# 02_-_MCU.net
KiCad netlist of a schematic drawn in Altium Designer
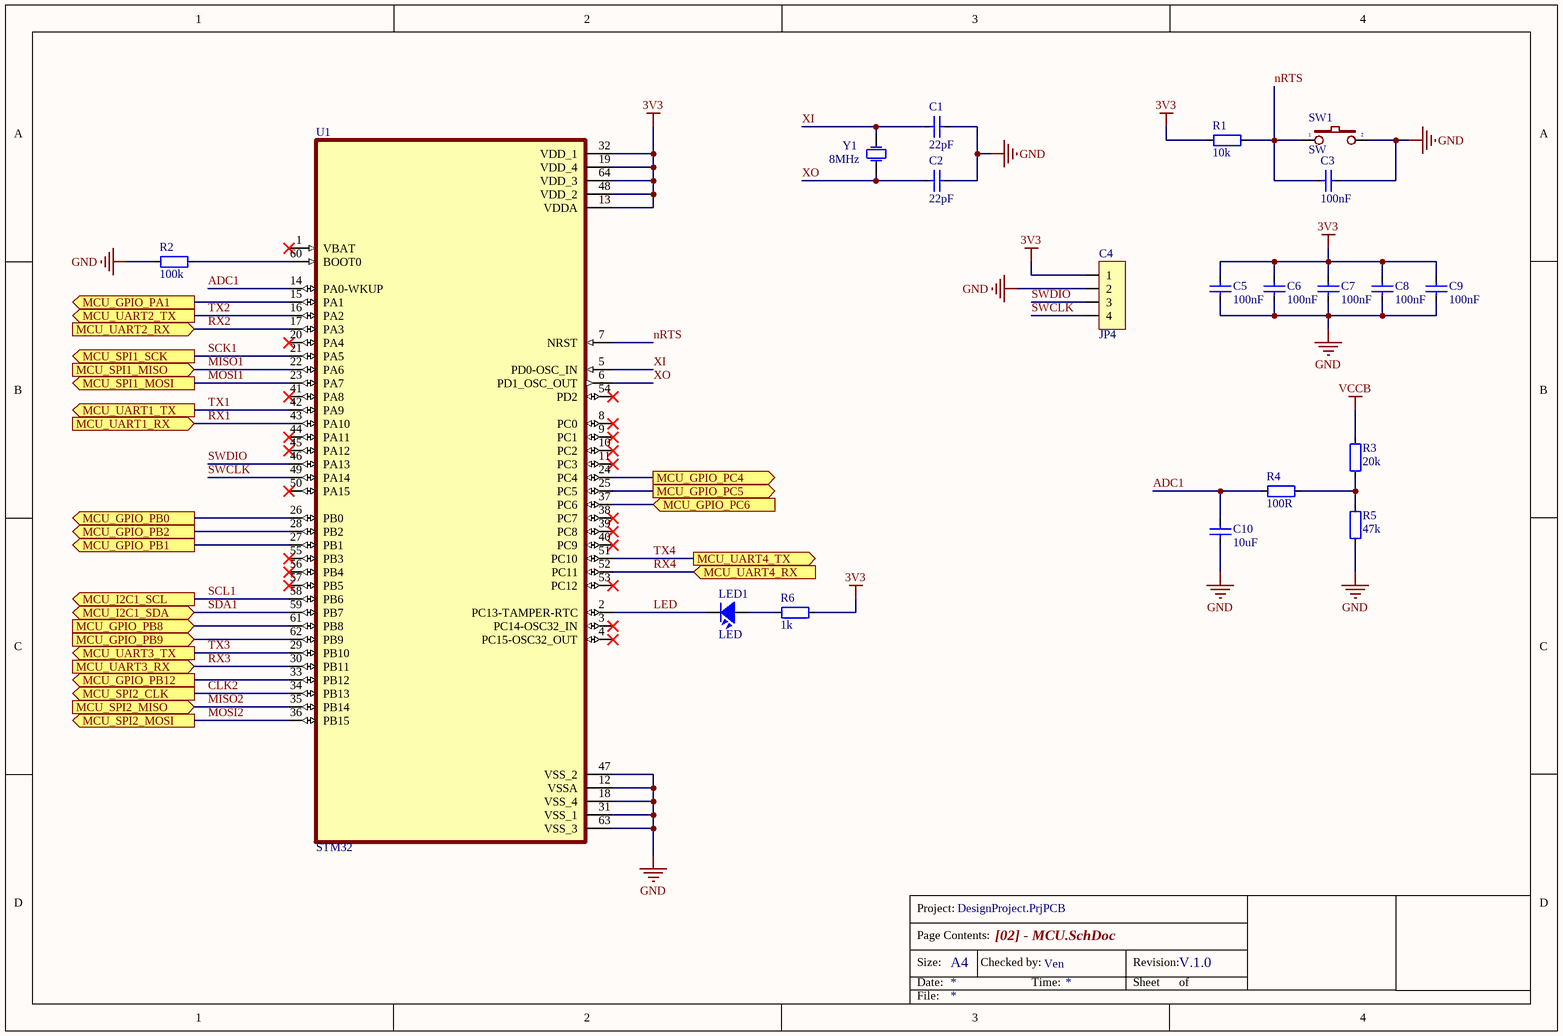
[diagram p0: [02] - MCU.SchDoc]

(export (version "E")
  (design (tool "Eeschema 10.0.6"))
  (components
    (comp (ref "C1")
      (value "22pF")
      (footprint "CAP_0603")
      (description "Capacitor")
      (fields (field (name "PUBLISHER") "Altium Limited"))
      (libsource (lib "My Library") (part "CapSMD"))
    )
    (comp (ref "C2")
      (value "22pF")
      (footprint "CAP_0603")
      (description "Capacitor")
      (fields (field (name "PUBLISHER") "Altium Limited"))
      (libsource (lib "My Library") (part "CapSMD"))
    )
    (comp (ref "C3")
      (value "100nF")
      (footprint "CAP_0603")
      (description "Capacitor")
      (fields (field (name "PUBLISHER") "Altium Limited"))
      (libsource (lib "My Library") (part "CapSMD"))
    )
    (comp (ref "C4")
      (value "JP4")
      (footprint "JP4-C1T")
      (description "WR-PHD 2.54 mm Angled Socket Header")
      (fields
        (field (name "MANUFACTURER") "Würth Elektronik eiSos GmbH")
        (field (name "PARTNO") "613004143121")
        (field (name "CREATED BY") "Karrer Zheng")
      )
      (libsource (lib "My Library") (part "JP4"))
    )
    (comp (ref "C5")
      (value "100nF")
      (footprint "CAP_0603")
      (description "Capacitor")
      (fields (field (name "PUBLISHER") "Altium Limited"))
      (libsource (lib "My Library") (part "CapSMD"))
    )
    (comp (ref "C6")
      (value "100nF")
      (footprint "CAP_0603")
      (description "Capacitor")
      (fields (field (name "PUBLISHER") "Altium Limited"))
      (libsource (lib "My Library") (part "CapSMD"))
    )
    (comp (ref "C7")
      (value "100nF")
      (footprint "CAP_0603")
      (description "Capacitor")
      (fields (field (name "PUBLISHER") "Altium Limited"))
      (libsource (lib "My Library") (part "CapSMD"))
    )
    (comp (ref "C8")
      (value "100nF")
      (footprint "CAP_0603")
      (description "Capacitor")
      (fields (field (name "PUBLISHER") "Altium Limited"))
      (libsource (lib "My Library") (part "CapSMD"))
    )
    (comp (ref "C9")
      (value "100nF")
      (footprint "CAP_0603")
      (description "Capacitor")
      (fields (field (name "PUBLISHER") "Altium Limited"))
      (libsource (lib "My Library") (part "CapSMD"))
    )
    (comp (ref "C10")
      (value "10uF")
      (footprint "CAP_0603")
      (description "Capacitor")
      (fields (field (name "PUBLISHER") "Altium Limited"))
      (libsource (lib "My Library") (part "CapSMD"))
    )
    (comp (ref "LED1")
      (value "LED")
      (footprint "LED-0805-Red")
      (description "LED Single colour Green and Red")
      (libsource (lib "My Library") (part "LED"))
    )
    (comp (ref "R1")
      (value "10k")
      (footprint "RES-SMD-0603")
      (description "Resistor")
      (fields
        (field (name "MANUFACTURER") "Generic Components")
        (field (name "PUBLISHER") "Altium Hobart Technology Centre")
      )
      (libsource (lib "My Library") (part "Resistor - SMD"))
    )
    (comp (ref "R2")
      (value "100k")
      (footprint "RES-SMD-0603")
      (description "Resistor")
      (fields
        (field (name "MANUFACTURER") "Generic Components")
        (field (name "PUBLISHER") "Altium Hobart Technology Centre")
      )
      (libsource (lib "My Library") (part "Resistor - SMD"))
    )
    (comp (ref "R3")
      (value "20k")
      (footprint "RES-SMD-0603")
      (description "Resistor")
      (fields
        (field (name "MANUFACTURER") "Generic Components")
        (field (name "PUBLISHER") "Altium Hobart Technology Centre")
      )
      (libsource (lib "My Library") (part "Resistor - SMD"))
    )
    (comp (ref "R4")
      (value "100R")
      (footprint "RES-SMD-0603")
      (description "Resistor")
      (fields
        (field (name "MANUFACTURER") "Generic Components")
        (field (name "PUBLISHER") "Altium Hobart Technology Centre")
      )
      (libsource (lib "My Library") (part "Resistor - SMD"))
    )
    (comp (ref "R5")
      (value "47k")
      (footprint "RES-SMD-0603")
      (description "Resistor")
      (fields
        (field (name "MANUFACTURER") "Generic Components")
        (field (name "PUBLISHER") "Altium Hobart Technology Centre")
      )
      (libsource (lib "My Library") (part "Resistor - SMD"))
    )
    (comp (ref "R6")
      (value "1k")
      (footprint "RES-SMD-0603")
      (description "Resistor")
      (fields
        (field (name "MANUFACTURER") "Generic Components")
        (field (name "PUBLISHER") "Altium Hobart Technology Centre")
      )
      (libsource (lib "My Library") (part "Resistor - SMD"))
    )
    (comp (ref "SW1")
      (value "SW")
      (footprint "SW2")
      (description "Switch button 2 pin")
      (libsource (lib "My Library") (part "SW2"))
    )
    (comp (ref "U1")
      (value "STM32")
      (footprint "QFP50P1200X1200X160-64N")
      (description "STM32 ARM-based 32-bit MCU 72MHz 256KB")
      (libsource (lib "My Library") (part "STM32F103RCT6"))
    )
    (comp (ref "Y1")
      (value "8MHz")
      (footprint "XTAL 5032 SMD")
      (description "Crystal Oscillator")
      (fields (field (name "PUBLISHER") "Altium Limited"))
      (libsource (lib "My Library") (part "XTAL"))
    )
  )
  (nets
    (net (code "1") (name "/ADC1") (class "Default")
      (node (ref "C10") (pin "1") (pinfunction "1_1") (pintype "passive"))
      (node (ref "R4") (pin "1") (pinfunction "1_1") (pintype "passive"))
      (node (ref "U1") (pin "14") (pinfunction "PA0-WKUP_14") (pintype "bidirectional"))
    )
    (net (code "2") (name "/CLK2") (class "Default")
      (node (ref "U1") (pin "34") (pinfunction "PB13_34") (pintype "bidirectional"))
    )
    (net (code "3") (name "/LED") (class "Default")
      (node (ref "LED1") (pin "2") (pinfunction "2_2") (pintype "passive"))
      (node (ref "U1") (pin "2") (pinfunction "PC13-TAMPER-RTC_2") (pintype "bidirectional"))
    )
    (net (code "4") (name "/MCU_GPIO_PA1") (class "Default")
      (node (ref "U1") (pin "15") (pinfunction "PA1_15") (pintype "bidirectional"))
    )
    (net (code "5") (name "/MCU_GPIO_PB0") (class "Default")
      (node (ref "U1") (pin "26") (pinfunction "PB0_26") (pintype "bidirectional"))
    )
    (net (code "6") (name "/MCU_GPIO_PB1") (class "Default")
      (node (ref "U1") (pin "27") (pinfunction "PB1_27") (pintype "bidirectional"))
    )
    (net (code "7") (name "/MCU_GPIO_PB2") (class "Default")
      (node (ref "U1") (pin "28") (pinfunction "PB2_28") (pintype "bidirectional"))
    )
    (net (code "8") (name "/MCU_GPIO_PB8") (class "Default")
      (node (ref "U1") (pin "61") (pinfunction "PB8_61") (pintype "bidirectional"))
    )
    (net (code "9") (name "/MCU_GPIO_PB9") (class "Default")
      (node (ref "U1") (pin "62") (pinfunction "PB9_62") (pintype "bidirectional"))
    )
    (net (code "10") (name "/MCU_GPIO_PB12") (class "Default")
      (node (ref "U1") (pin "33") (pinfunction "PB12_33") (pintype "bidirectional"))
    )
    (net (code "11") (name "/MCU_GPIO_PC4") (class "Default")
      (node (ref "U1") (pin "24") (pinfunction "PC4_24") (pintype "bidirectional"))
    )
    (net (code "12") (name "/MCU_GPIO_PC5") (class "Default")
      (node (ref "U1") (pin "25") (pinfunction "PC5_25") (pintype "bidirectional"))
    )
    (net (code "13") (name "/MCU_GPIO_PC6") (class "Default")
      (node (ref "U1") (pin "37") (pinfunction "PC6_37") (pintype "bidirectional"))
    )
    (net (code "14") (name "/MISO1") (class "Default")
      (node (ref "U1") (pin "22") (pinfunction "PA6_22") (pintype "bidirectional"))
    )
    (net (code "15") (name "/MISO2") (class "Default")
      (node (ref "U1") (pin "35") (pinfunction "PB14_35") (pintype "bidirectional"))
    )
    (net (code "16") (name "/MOSI1") (class "Default")
      (node (ref "U1") (pin "23") (pinfunction "PA7_23") (pintype "bidirectional"))
    )
    (net (code "17") (name "/MOSI2") (class "Default")
      (node (ref "U1") (pin "36") (pinfunction "PB15_36") (pintype "bidirectional"))
    )
    (net (code "18") (name "/RX1") (class "Default")
      (node (ref "U1") (pin "43") (pinfunction "PA10_43") (pintype "bidirectional"))
    )
    (net (code "19") (name "/RX2") (class "Default")
      (node (ref "U1") (pin "17") (pinfunction "PA3_17") (pintype "bidirectional"))
    )
    (net (code "20") (name "/RX3") (class "Default")
      (node (ref "U1") (pin "30") (pinfunction "PB11_30") (pintype "bidirectional"))
    )
    (net (code "21") (name "/RX4") (class "Default")
      (node (ref "U1") (pin "52") (pinfunction "PC11_52") (pintype "bidirectional"))
    )
    (net (code "22") (name "/SCK1") (class "Default")
      (node (ref "U1") (pin "21") (pinfunction "PA5_21") (pintype "bidirectional"))
    )
    (net (code "23") (name "/SCL1") (class "Default")
      (node (ref "U1") (pin "58") (pinfunction "PB6_58") (pintype "bidirectional"))
    )
    (net (code "24") (name "/SDA1") (class "Default")
      (node (ref "U1") (pin "59") (pinfunction "PB7_59") (pintype "bidirectional"))
    )
    (net (code "25") (name "/SWCLK") (class "Default")
      (node (ref "C4") (pin "4") (pinfunction "4_4") (pintype "passive"))
      (node (ref "U1") (pin "49") (pinfunction "PA14_49") (pintype "bidirectional"))
    )
    (net (code "26") (name "/SWDIO") (class "Default")
      (node (ref "C4") (pin "3") (pinfunction "3_3") (pintype "passive"))
      (node (ref "U1") (pin "46") (pinfunction "PA13_46") (pintype "bidirectional"))
    )
    (net (code "27") (name "/TX1") (class "Default")
      (node (ref "U1") (pin "42") (pinfunction "PA9_42") (pintype "bidirectional"))
    )
    (net (code "28") (name "/TX2") (class "Default")
      (node (ref "U1") (pin "16") (pinfunction "PA2_16") (pintype "bidirectional"))
    )
    (net (code "29") (name "/TX3") (class "Default")
      (node (ref "U1") (pin "29") (pinfunction "PB10_29") (pintype "bidirectional"))
    )
    (net (code "30") (name "/TX4") (class "Default")
      (node (ref "U1") (pin "51") (pinfunction "PC10_51") (pintype "bidirectional"))
    )
    (net (code "31") (name "/XI") (class "Default")
      (node (ref "C1") (pin "2") (pinfunction "2_2") (pintype "passive"))
      (node (ref "U1") (pin "5") (pinfunction "PD0-OSC_IN_5") (pintype "input"))
      (node (ref "Y1") (pin "2") (pinfunction "OSC2_2") (pintype "passive"))
    )
    (net (code "32") (name "/XO") (class "Default")
      (node (ref "C2") (pin "2") (pinfunction "2_2") (pintype "passive"))
      (node (ref "U1") (pin "6") (pinfunction "PD1_OSC_OUT_6") (pintype "output"))
      (node (ref "Y1") (pin "1") (pinfunction "OSC1_1") (pintype "passive"))
    )
    (net (code "33") (name "/nRTS") (class "Default")
      (node (ref "C3") (pin "2") (pinfunction "2_2") (pintype "passive"))
      (node (ref "R1") (pin "2") (pinfunction "2_2") (pintype "passive"))
      (node (ref "SW1") (pin "1") (pinfunction "1_1") (pintype "passive"))
      (node (ref "U1") (pin "7") (pinfunction "NRST_7") (pintype "input"))
    )
    (net (code "34") (name "3V3") (class "Default")
      (node (ref "C4") (pin "1") (pinfunction "1_1") (pintype "passive"))
      (node (ref "C5") (pin "2") (pinfunction "2_2") (pintype "passive"))
      (node (ref "C6") (pin "2") (pinfunction "2_2") (pintype "passive"))
      (node (ref "C7") (pin "2") (pinfunction "2_2") (pintype "passive"))
      (node (ref "C8") (pin "2") (pinfunction "2_2") (pintype "passive"))
      (node (ref "C9") (pin "2") (pinfunction "2_2") (pintype "passive"))
      (node (ref "R1") (pin "1") (pinfunction "1_1") (pintype "passive"))
      (node (ref "R6") (pin "1") (pinfunction "1_1") (pintype "passive"))
      (node (ref "U1") (pin "13") (pinfunction "VDDA_13") (pintype "power_in"))
      (node (ref "U1") (pin "19") (pinfunction "VDD_4_19") (pintype "power_in"))
      (node (ref "U1") (pin "32") (pinfunction "VDD_1_32") (pintype "power_in"))
      (node (ref "U1") (pin "48") (pinfunction "VDD_2_48") (pintype "power_in"))
      (node (ref "U1") (pin "64") (pinfunction "VDD_3_64") (pintype "power_in"))
    )
    (net (code "35") (name "GND") (class "Default")
      (node (ref "C1") (pin "1") (pinfunction "1_1") (pintype "passive"))
      (node (ref "C10") (pin "2") (pinfunction "2_2") (pintype "passive"))
      (node (ref "C2") (pin "1") (pinfunction "1_1") (pintype "passive"))
      (node (ref "C3") (pin "1") (pinfunction "1_1") (pintype "passive"))
      (node (ref "C4") (pin "2") (pinfunction "2_2") (pintype "passive"))
      (node (ref "C5") (pin "1") (pinfunction "1_1") (pintype "passive"))
      (node (ref "C6") (pin "1") (pinfunction "1_1") (pintype "passive"))
      (node (ref "C7") (pin "1") (pinfunction "1_1") (pintype "passive"))
      (node (ref "C8") (pin "1") (pinfunction "1_1") (pintype "passive"))
      (node (ref "C9") (pin "1") (pinfunction "1_1") (pintype "passive"))
      (node (ref "R2") (pin "1") (pinfunction "1_1") (pintype "passive"))
      (node (ref "R5") (pin "2") (pinfunction "2_2") (pintype "passive"))
      (node (ref "SW1") (pin "2") (pinfunction "2_2") (pintype "passive"))
      (node (ref "U1") (pin "12") (pinfunction "VSSA_12") (pintype "power_in"))
      (node (ref "U1") (pin "18") (pinfunction "VSS_4_18") (pintype "power_in"))
      (node (ref "U1") (pin "31") (pinfunction "VSS_1_31") (pintype "power_in"))
      (node (ref "U1") (pin "47") (pinfunction "VSS_2_47") (pintype "power_in"))
      (node (ref "U1") (pin "63") (pinfunction "VSS_3_63") (pintype "power_in"))
    )
    (net (code "36") (name "Net-(LED1-Pad1)") (class "Default")
      (node (ref "LED1") (pin "1") (pinfunction "1_1") (pintype "passive"))
      (node (ref "R6") (pin "2") (pinfunction "2_2") (pintype "passive"))
    )
    (net (code "37") (name "Net-(R3-Pad2)") (class "Default")
      (node (ref "R3") (pin "2") (pinfunction "2_2") (pintype "passive"))
      (node (ref "R4") (pin "2") (pinfunction "2_2") (pintype "passive"))
      (node (ref "R5") (pin "1") (pinfunction "1_1") (pintype "passive"))
    )
    (net (code "38") (name "Net-(U1-BOOT0)") (class "Default")
      (node (ref "R2") (pin "2") (pinfunction "2_2") (pintype "passive"))
      (node (ref "U1") (pin "60") (pinfunction "BOOT0_60") (pintype "input"))
    )
    (net (code "39") (name "VCCB") (class "Default")
      (node (ref "R3") (pin "1") (pinfunction "1_1") (pintype "passive"))
    )
    (net (code "40") (name "unconnected-(U1-PA4-Pad20)") (class "Default")
      (node (ref "U1") (pin "20") (pinfunction "PA4_20") (pintype "bidirectional+no_connect"))
    )
    (net (code "41") (name "unconnected-(U1-PA8-Pad41)") (class "Default")
      (node (ref "U1") (pin "41") (pinfunction "PA8_41") (pintype "bidirectional+no_connect"))
    )
    (net (code "42") (name "unconnected-(U1-PA11-Pad44)") (class "Default")
      (node (ref "U1") (pin "44") (pinfunction "PA11_44") (pintype "bidirectional+no_connect"))
    )
    (net (code "43") (name "unconnected-(U1-PA12-Pad45)") (class "Default")
      (node (ref "U1") (pin "45") (pinfunction "PA12_45") (pintype "bidirectional+no_connect"))
    )
    (net (code "44") (name "unconnected-(U1-PA15-Pad50)") (class "Default")
      (node (ref "U1") (pin "50") (pinfunction "PA15_50") (pintype "bidirectional+no_connect"))
    )
    (net (code "45") (name "unconnected-(U1-PB3-Pad55)") (class "Default")
      (node (ref "U1") (pin "55") (pinfunction "PB3_55") (pintype "bidirectional+no_connect"))
    )
    (net (code "46") (name "unconnected-(U1-PB4-Pad56)") (class "Default")
      (node (ref "U1") (pin "56") (pinfunction "PB4_56") (pintype "bidirectional+no_connect"))
    )
    (net (code "47") (name "unconnected-(U1-PB5-Pad57)") (class "Default")
      (node (ref "U1") (pin "57") (pinfunction "PB5_57") (pintype "bidirectional+no_connect"))
    )
    (net (code "48") (name "unconnected-(U1-PC0-Pad8)") (class "Default")
      (node (ref "U1") (pin "8") (pinfunction "PC0_8") (pintype "bidirectional+no_connect"))
    )
    (net (code "49") (name "unconnected-(U1-PC1-Pad9)") (class "Default")
      (node (ref "U1") (pin "9") (pinfunction "PC1_9") (pintype "bidirectional+no_connect"))
    )
    (net (code "50") (name "unconnected-(U1-PC2-Pad10)") (class "Default")
      (node (ref "U1") (pin "10") (pinfunction "PC2_10") (pintype "bidirectional+no_connect"))
    )
    (net (code "51") (name "unconnected-(U1-PC3-Pad11)") (class "Default")
      (node (ref "U1") (pin "11") (pinfunction "PC3_11") (pintype "bidirectional+no_connect"))
    )
    (net (code "52") (name "unconnected-(U1-PC7-Pad38)") (class "Default")
      (node (ref "U1") (pin "38") (pinfunction "PC7_38") (pintype "bidirectional+no_connect"))
    )
    (net (code "53") (name "unconnected-(U1-PC8-Pad39)") (class "Default")
      (node (ref "U1") (pin "39") (pinfunction "PC8_39") (pintype "bidirectional+no_connect"))
    )
    (net (code "54") (name "unconnected-(U1-PC9-Pad40)") (class "Default")
      (node (ref "U1") (pin "40") (pinfunction "PC9_40") (pintype "bidirectional+no_connect"))
    )
    (net (code "55") (name "unconnected-(U1-PC12-Pad53)") (class "Default")
      (node (ref "U1") (pin "53") (pinfunction "PC12_53") (pintype "bidirectional+no_connect"))
    )
    (net (code "56") (name "unconnected-(U1-PC14-OSC32_IN-Pad3)") (class "Default")
      (node (ref "U1") (pin "3") (pinfunction "PC14-OSC32_IN_3") (pintype "bidirectional+no_connect"))
    )
    (net (code "57") (name "unconnected-(U1-PC15-OSC32_OUT-Pad4)") (class "Default")
      (node (ref "U1") (pin "4") (pinfunction "PC15-OSC32_OUT_4") (pintype "bidirectional+no_connect"))
    )
    (net (code "58") (name "unconnected-(U1-PD2-Pad54)") (class "Default")
      (node (ref "U1") (pin "54") (pinfunction "PD2_54") (pintype "bidirectional+no_connect"))
    )
    (net (code "59") (name "unconnected-(U1-VBAT-Pad1)") (class "Default")
      (node (ref "U1") (pin "1") (pinfunction "VBAT_1") (pintype "input+no_connect"))
    )
  )
)
